# Docking_Connection.net
KiCad netlist of a schematic drawn in Altium Designer
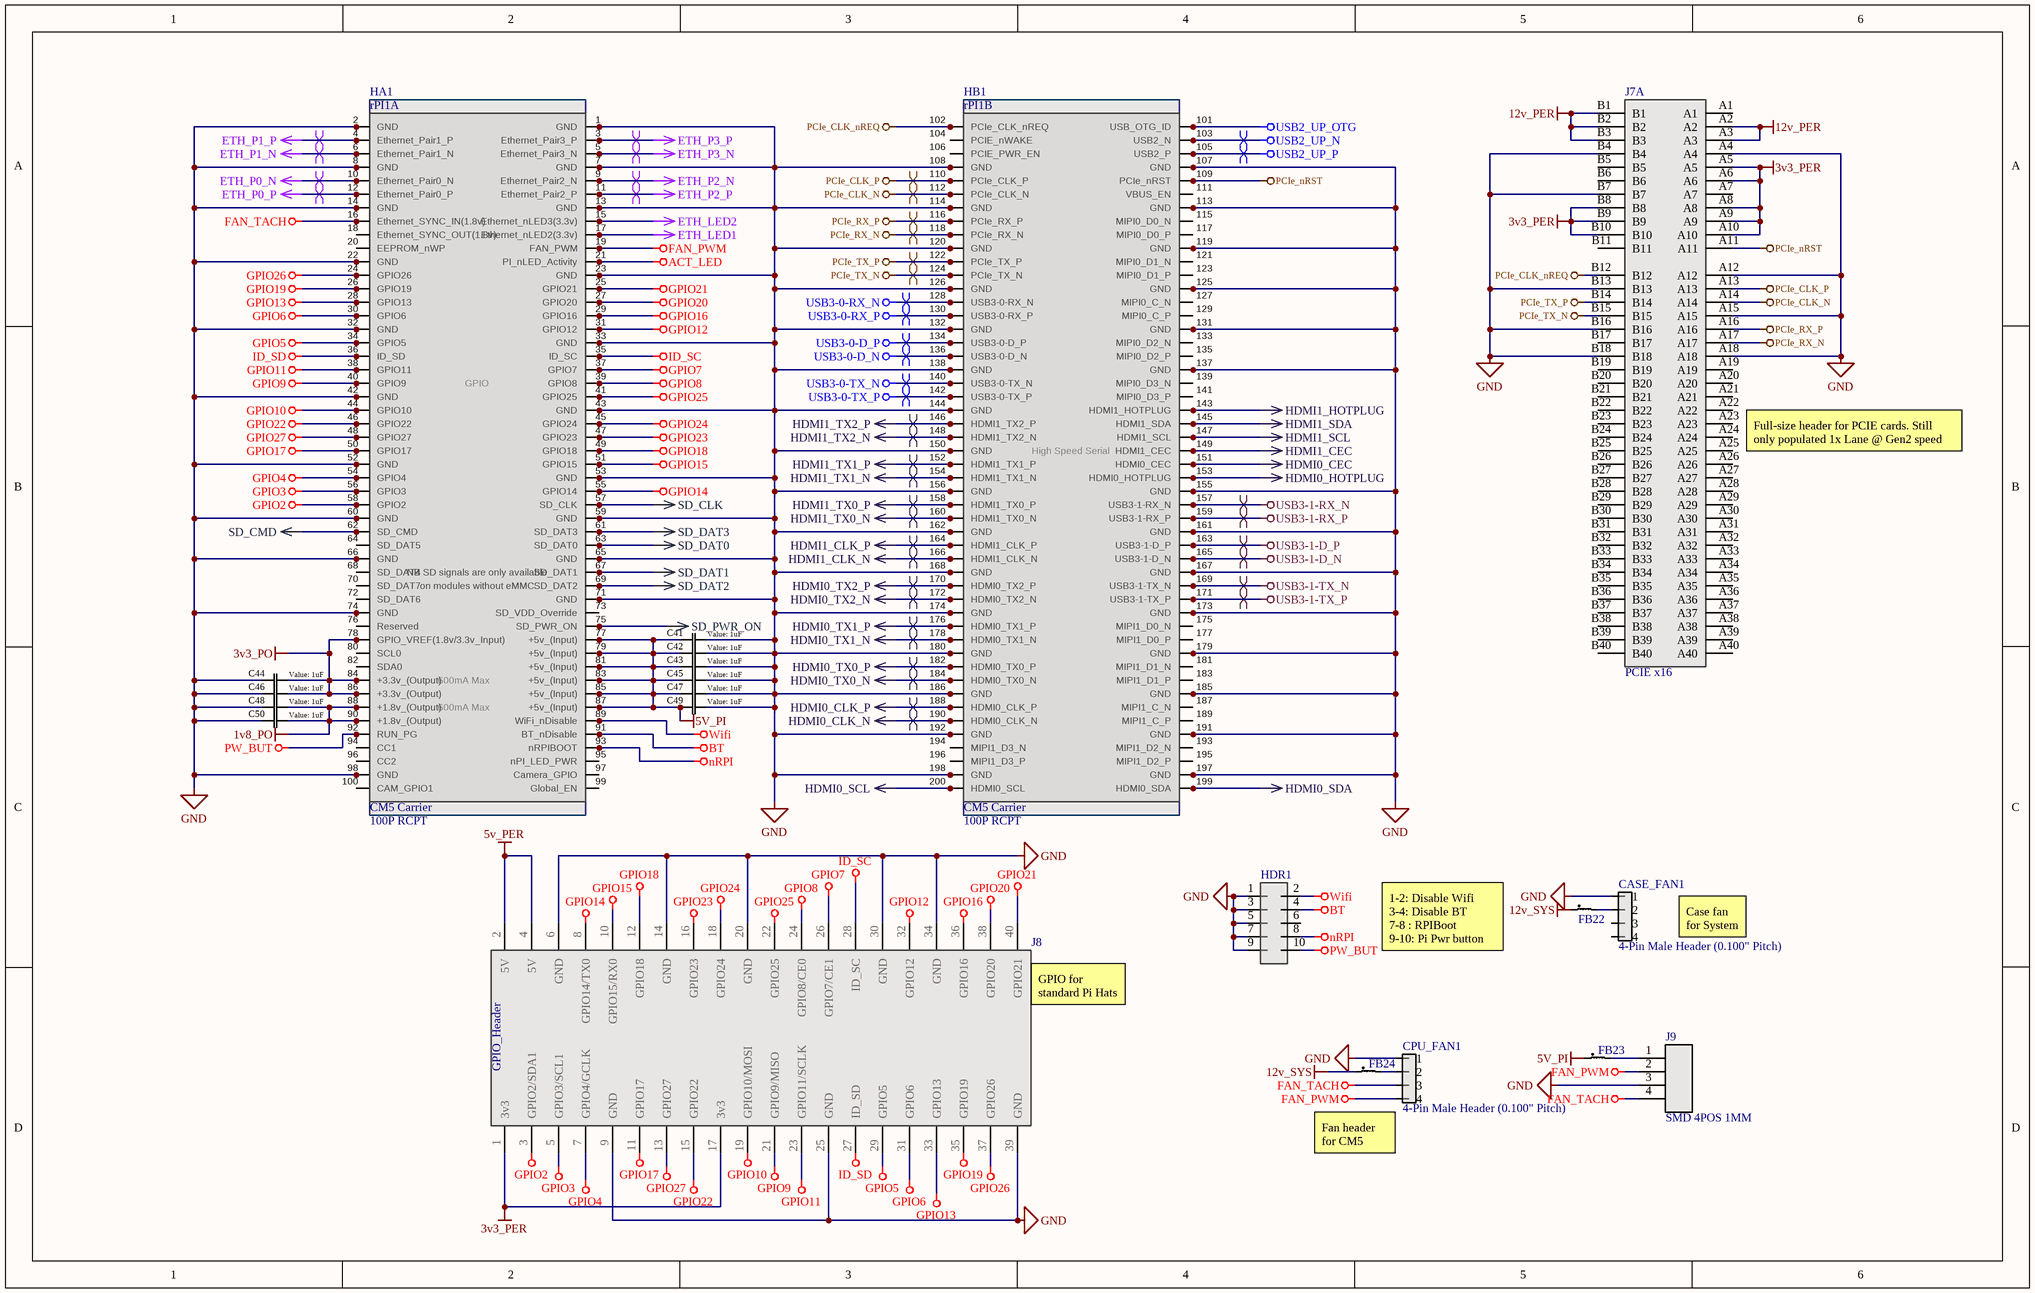
[diagram p0: Docking_Connection.SchDoc]

(export (version "E")
  (design (tool "Eeschema 10.0.6"))
  (components
    (comp (ref "C41")
      (value "1uF")
      (footprint "0603")
      (fields
        (field (name "VOLTAGE") "6V")
        (field (name "TOLERANCE") "5%")
        (field (name "Comment") "Generic Capacitor")
      )
      (libsource (lib "Capacitors") (part "Generic Capacitor"))
    )
    (comp (ref "C42")
      (value "1uF")
      (footprint "0603")
      (fields
        (field (name "VOLTAGE") "6V")
        (field (name "TOLERANCE") "5%")
        (field (name "Comment") "Generic Capacitor")
      )
      (libsource (lib "Capacitors") (part "Generic Capacitor"))
    )
    (comp (ref "C43")
      (value "1uF")
      (footprint "0603")
      (fields
        (field (name "VOLTAGE") "6V")
        (field (name "TOLERANCE") "5%")
        (field (name "Comment") "Generic Capacitor")
      )
      (libsource (lib "Capacitors") (part "Generic Capacitor"))
    )
    (comp (ref "C44")
      (value "1uF")
      (footprint "0603")
      (fields
        (field (name "VOLTAGE") "6V")
        (field (name "TOLERANCE") "5%")
        (field (name "Comment") "Generic Capacitor")
      )
      (libsource (lib "Capacitors") (part "Generic Capacitor"))
    )
    (comp (ref "C45")
      (value "1uF")
      (footprint "0603")
      (fields
        (field (name "VOLTAGE") "6V")
        (field (name "TOLERANCE") "5%")
        (field (name "Comment") "Generic Capacitor")
      )
      (libsource (lib "Capacitors") (part "Generic Capacitor"))
    )
    (comp (ref "C46")
      (value "1uF")
      (footprint "0603")
      (fields
        (field (name "VOLTAGE") "6V")
        (field (name "TOLERANCE") "5%")
        (field (name "Comment") "Generic Capacitor")
      )
      (libsource (lib "Capacitors") (part "Generic Capacitor"))
    )
    (comp (ref "C47")
      (value "1uF")
      (footprint "0603")
      (fields
        (field (name "VOLTAGE") "6V")
        (field (name "TOLERANCE") "5%")
        (field (name "Comment") "Generic Capacitor")
      )
      (libsource (lib "Capacitors") (part "Generic Capacitor"))
    )
    (comp (ref "C48")
      (value "1uF")
      (footprint "0603")
      (fields
        (field (name "VOLTAGE") "6V")
        (field (name "TOLERANCE") "5%")
        (field (name "Comment") "Generic Capacitor")
      )
      (libsource (lib "Capacitors") (part "Generic Capacitor"))
    )
    (comp (ref "C49")
      (value "1uF")
      (footprint "0603")
      (fields
        (field (name "VOLTAGE") "6V")
        (field (name "TOLERANCE") "5%")
        (field (name "Comment") "Generic Capacitor")
      )
      (libsource (lib "Capacitors") (part "Generic Capacitor"))
    )
    (comp (ref "C50")
      (value "1uF")
      (footprint "0603")
      (fields
        (field (name "VOLTAGE") "6V")
        (field (name "TOLERANCE") "5%")
        (field (name "Comment") "Generic Capacitor")
      )
      (libsource (lib "Capacitors") (part "Generic Capacitor"))
    )
    (comp (ref "CASE_FAN1")
      (value "4-Pin Male Header (0.100\" Pitch)")
      (footprint "TSW-104-07-T-S")
      (description "Connector Header Through Hole 4 position 0.100\" (2.54mm)")
      (libsource (lib "Connectors") (part "TSW-104-07-T-S"))
    )
    (comp (ref "CPU_FAN1")
      (value "4-Pin Male Header (0.100\" Pitch)")
      (footprint "TSW-104-07-T-S")
      (description "Connector Header Through Hole 4 position 0.100\" (2.54mm)")
      (libsource (lib "Connectors") (part "TSW-104-07-T-S"))
    )
    (comp (ref "FB22")
      (value "0603 Ferrite")
      (footprint "0603")
      (description "120 Ohms @ 100 MHz 1 Signal Line Ferrite Bead 0603 (1608 Metric) 500mA 180mOhm")
      (fields
        (field (name "MANUFACTURER") "Pulse")
        (field (name "MANUFACTURER PART NUMBER") "PE-0603FB121ST")
      )
      (libsource (lib "Inductors") (part "PE-0603FB121ST"))
    )
    (comp (ref "FB23")
      (value "0603 Ferrite")
      (footprint "0603")
      (description "120 Ohms @ 100 MHz 1 Signal Line Ferrite Bead 0603 (1608 Metric) 500mA 180mOhm")
      (fields
        (field (name "MANUFACTURER") "Pulse")
        (field (name "MANUFACTURER PART NUMBER") "PE-0603FB121ST")
      )
      (libsource (lib "Inductors") (part "PE-0603FB121ST"))
    )
    (comp (ref "FB24")
      (value "0603 Ferrite")
      (footprint "0603")
      (description "120 Ohms @ 100 MHz 1 Signal Line Ferrite Bead 0603 (1608 Metric) 500mA 180mOhm")
      (fields
        (field (name "MANUFACTURER") "Pulse")
        (field (name "MANUFACTURER PART NUMBER") "PE-0603FB121ST")
      )
      (libsource (lib "Inductors") (part "PE-0603FB121ST"))
    )
    (comp (ref "HA1")
      (value "100P RCPT")
      (footprint "DF40HC(3.0)-100DS-0.4V(51)")
      (description "100 Position Connector Receptacle, Center Strip Contacts Surface Mount Gold")
      (fields (field (name "MF") "Hirose") (field (name "MP") "DF40C-100DS-0.4V(51)"))
      (libsource (lib "Connectors") (part "DF40-100DS RCPT_1"))
    )
    (comp (ref "HB1")
      (value "100P RCPT")
      (footprint "DF40HC(3.0)-100DS-0.4V(51)")
      (description "100 Position Connector Receptacle, Center Strip Contacts Surface Mount Gold")
      (fields (field (name "MF") "Hirose") (field (name "MP") "DF40C-100DS-0.4V(51)"))
      (libsource (lib "Connectors") (part "DF40-100DS RCPT_1"))
    )
    (comp (ref "HDR1")
      (value "10pinMobo")
      (footprint "10pinMobo")
      (description "10pin motherboard jack")
      (libsource (lib "Connectors") (part "10pinMobo"))
    )
    (comp (ref "J7")
      (value "PCIE x16")
      (footprint "10018783-10203TLF")
      (description "164 Position Female Connector PCI Express™ Gold 0.039\" (1.00mm) Black")
      (fields (field (name "MF") "Amphenol ICC") (field (name "MP") "10018783-10203TLF"))
      (libsource (lib "Connectors") (part "10018783-10203TLF"))
    )
    (comp (ref "J8")
      (value "rPi Zero Carrier")
      (footprint "rPiHeader")
      (description "Raspberry Pi Zero/W/2W\r\nHeader, debug-pads, & mounting")
      (libsource (lib "SOC_Carrier") (part "RP-Zero_1"))
    )
    (comp (ref "J9")
      (value "SMD 4POS 1MM")
      (footprint "CONN4_BM04B-SRSS_JST")
      (description "Connector Header Surface Mount 4 position 0.039\" (1.00mm)")
      (libsource (lib "Connectors") (part "BM04B-SRSS-TB"))
    )
    (comp (ref "rPI1")
      (value "CM5 Carrier")
      (footprint "CM4-FTPD")
      (description "Compute Module 5 Footprint\r\nOverlap Hirose 100P connector over pads to place actual components")
      (libsource (lib "Misc ICs") (part "RP-CM5"))
    )
  )
  (nets
    (net (code "1") (name "1v8_PO") (class "Default")
      (node (ref "C48") (pin "1") (pinfunction "1_1") (pintype "passive"))
      (node (ref "C50") (pin "1") (pinfunction "1_1") (pintype "passive"))
      (node (ref "HA1") (pin "88") (pinfunction "88_88") (pintype "passive"))
      (node (ref "HA1") (pin "90") (pinfunction "90_90") (pintype "passive"))
      (node (ref "rPI1") (pin "88") (pinfunction "+1.8v_(Output)_88") (pintype "passive"))
      (node (ref "rPI1") (pin "90") (pinfunction "+1.8v_(Output)_90") (pintype "passive"))
    )
    (net (code "2") (name "3v3_PER") (class "Default")
      (node (ref "J7") (pin "A10") (pinfunction "A10_A10") (pintype "passive"))
      (node (ref "J7") (pin "A5") (pinfunction "A5_A5") (pintype "passive"))
      (node (ref "J7") (pin "A6") (pinfunction "A6_A6") (pintype "passive"))
      (node (ref "J7") (pin "A8") (pinfunction "A8_A8") (pintype "passive"))
      (node (ref "J7") (pin "A9") (pinfunction "A9_A9") (pintype "passive"))
      (node (ref "J7") (pin "B10") (pinfunction "B10_B10") (pintype "passive"))
      (node (ref "J7") (pin "B8") (pinfunction "B8_B8") (pintype "passive"))
      (node (ref "J7") (pin "B9") (pinfunction "B9_B9") (pintype "passive"))
      (node (ref "J8") (pin "1") (pinfunction "3v3_1") (pintype "passive"))
      (node (ref "J8") (pin "17") (pinfunction "3v3_17") (pintype "passive"))
    )
    (net (code "3") (name "3v3_PO") (class "Default")
      (node (ref "C44") (pin "1") (pinfunction "1_1") (pintype "passive"))
      (node (ref "C46") (pin "1") (pinfunction "1_1") (pintype "passive"))
      (node (ref "HA1") (pin "78") (pinfunction "78_78") (pintype "passive"))
      (node (ref "HA1") (pin "84") (pinfunction "84_84") (pintype "passive"))
      (node (ref "HA1") (pin "86") (pinfunction "86_86") (pintype "passive"))
      (node (ref "rPI1") (pin "78") (pinfunction "GPIO_VREF(1.8v/3.3v_Input)_78") (pintype "passive"))
      (node (ref "rPI1") (pin "84") (pinfunction "+3.3v_(Output)_84") (pintype "passive"))
      (node (ref "rPI1") (pin "86") (pinfunction "+3.3v_(Output)_86") (pintype "passive"))
    )
    (net (code "4") (name "5V_PI") (class "Default")
      (node (ref "C41") (pin "2") (pinfunction "2_2") (pintype "passive"))
      (node (ref "C42") (pin "2") (pinfunction "2_2") (pintype "passive"))
      (node (ref "C43") (pin "2") (pinfunction "2_2") (pintype "passive"))
      (node (ref "C45") (pin "2") (pinfunction "2_2") (pintype "passive"))
      (node (ref "C47") (pin "2") (pinfunction "2_2") (pintype "passive"))
      (node (ref "C49") (pin "2") (pinfunction "2_2") (pintype "passive"))
      (node (ref "FB23") (pin "1") (pinfunction "1_1") (pintype "passive"))
      (node (ref "HA1") (pin "77") (pinfunction "77_77") (pintype "passive"))
      (node (ref "HA1") (pin "79") (pinfunction "79_79") (pintype "passive"))
      (node (ref "HA1") (pin "81") (pinfunction "81_81") (pintype "passive"))
      (node (ref "HA1") (pin "83") (pinfunction "83_83") (pintype "passive"))
      (node (ref "HA1") (pin "85") (pinfunction "85_85") (pintype "passive"))
      (node (ref "HA1") (pin "87") (pinfunction "87_87") (pintype "passive"))
      (node (ref "rPI1") (pin "77") (pinfunction "+5v_(Input)_77") (pintype "passive"))
      (node (ref "rPI1") (pin "79") (pinfunction "+5v_(Input)_79") (pintype "passive"))
      (node (ref "rPI1") (pin "81") (pinfunction "+5v_(Input)_81") (pintype "passive"))
      (node (ref "rPI1") (pin "83") (pinfunction "+5v_(Input)_83") (pintype "passive"))
      (node (ref "rPI1") (pin "85") (pinfunction "+5v_(Input)_85") (pintype "passive"))
      (node (ref "rPI1") (pin "87") (pinfunction "+5v_(Input)_87") (pintype "passive"))
    )
    (net (code "5") (name "5v_PER") (class "Default")
      (node (ref "J8") (pin "2") (pinfunction "5V_2") (pintype "passive"))
      (node (ref "J8") (pin "4") (pinfunction "5V_4") (pintype "passive"))
    )
    (net (code "6") (name "12v_PER") (class "Default")
      (node (ref "J7") (pin "A2") (pinfunction "A2_A2") (pintype "passive"))
      (node (ref "J7") (pin "A3") (pinfunction "A3_A3") (pintype "passive"))
      (node (ref "J7") (pin "B1") (pinfunction "B1_B1") (pintype "passive"))
      (node (ref "J7") (pin "B2") (pinfunction "B2_B2") (pintype "passive"))
      (node (ref "J7") (pin "B3") (pinfunction "B3_B3") (pintype "passive"))
    )
    (net (code "7") (name "12v_SYS") (class "Default")
      (node (ref "FB22") (pin "1") (pinfunction "1_1") (pintype "passive"))
      (node (ref "FB24") (pin "1") (pinfunction "1_1") (pintype "passive"))
    )
    (net (code "8") (name "ACT_LED") (class "Default")
      (node (ref "HA1") (pin "21") (pinfunction "21_21") (pintype "passive"))
      (node (ref "rPI1") (pin "21") (pinfunction "PI_nLED_Activity_21") (pintype "passive"))
    )
    (net (code "9") (name "BT") (class "Default")
      (node (ref "HA1") (pin "91") (pinfunction "91_91") (pintype "passive"))
      (node (ref "HDR1") (pin "4") (pinfunction "4_4") (pintype "passive"))
      (node (ref "rPI1") (pin "91") (pinfunction "BT_nDisable_91") (pintype "passive"))
    )
    (net (code "10") (name "ETH_LED1") (class "Default")
      (node (ref "HA1") (pin "17") (pinfunction "17_17") (pintype "passive"))
      (node (ref "rPI1") (pin "17") (pinfunction "Ethernet_nLED2(3.3v)_17") (pintype "passive"))
    )
    (net (code "11") (name "ETH_LED2") (class "Default")
      (node (ref "HA1") (pin "15") (pinfunction "15_15") (pintype "passive"))
      (node (ref "rPI1") (pin "15") (pinfunction "Ethernet_nLED3(3.3v)_15") (pintype "passive"))
    )
    (net (code "12") (name "ETH_P0_N") (class "Default")
      (node (ref "HA1") (pin "10") (pinfunction "10_10") (pintype "passive"))
      (node (ref "rPI1") (pin "10") (pinfunction "Ethernet_Pair0_N_10") (pintype "passive"))
    )
    (net (code "13") (name "ETH_P0_P") (class "Default")
      (node (ref "HA1") (pin "12") (pinfunction "12_12") (pintype "passive"))
      (node (ref "rPI1") (pin "12") (pinfunction "Ethernet_Pair0_P_12") (pintype "passive"))
    )
    (net (code "14") (name "ETH_P1_N") (class "Default")
      (node (ref "HA1") (pin "6") (pinfunction "6_6") (pintype "passive"))
      (node (ref "rPI1") (pin "6") (pinfunction "Ethernet_Pair1_N_6") (pintype "passive"))
    )
    (net (code "15") (name "ETH_P1_P") (class "Default")
      (node (ref "HA1") (pin "4") (pinfunction "4_4") (pintype "passive"))
      (node (ref "rPI1") (pin "4") (pinfunction "Ethernet_Pair1_P_4") (pintype "passive"))
    )
    (net (code "16") (name "ETH_P2_N") (class "Default")
      (node (ref "HA1") (pin "9") (pinfunction "9_9") (pintype "passive"))
      (node (ref "rPI1") (pin "9") (pinfunction "Ethernet_Pair2_N_9") (pintype "passive"))
    )
    (net (code "17") (name "ETH_P2_P") (class "Default")
      (node (ref "HA1") (pin "11") (pinfunction "11_11") (pintype "passive"))
      (node (ref "rPI1") (pin "11") (pinfunction "Ethernet_Pair2_P_11") (pintype "passive"))
    )
    (net (code "18") (name "ETH_P3_N") (class "Default")
      (node (ref "HA1") (pin "5") (pinfunction "5_5") (pintype "passive"))
      (node (ref "rPI1") (pin "5") (pinfunction "Ethernet_Pair3_N_5") (pintype "passive"))
    )
    (net (code "19") (name "ETH_P3_P") (class "Default")
      (node (ref "HA1") (pin "3") (pinfunction "3_3") (pintype "passive"))
      (node (ref "rPI1") (pin "3") (pinfunction "Ethernet_Pair3_P_3") (pintype "passive"))
    )
    (net (code "20") (name "FAN_PWM") (class "Default")
      (node (ref "CPU_FAN1") (pin "4") (pinfunction "4_4") (pintype "passive"))
      (node (ref "HA1") (pin "19") (pinfunction "19_19") (pintype "passive"))
      (node (ref "J9") (pin "2") (pinfunction "2_2") (pintype "passive"))
      (node (ref "rPI1") (pin "19") (pinfunction "FAN_PWM_19") (pintype "passive"))
    )
    (net (code "21") (name "FAN_TACH") (class "Default")
      (node (ref "CPU_FAN1") (pin "3") (pinfunction "3_3") (pintype "passive"))
      (node (ref "HA1") (pin "16") (pinfunction "16_16") (pintype "passive"))
      (node (ref "J9") (pin "4") (pinfunction "4_4") (pintype "passive"))
      (node (ref "rPI1") (pin "16") (pinfunction "Ethernet_SYNC_IN(1.8v)_16") (pintype "passive"))
    )
    (net (code "22") (name "GND") (class "Default")
      (node (ref "C41") (pin "1") (pinfunction "1_1") (pintype "passive"))
      (node (ref "C42") (pin "1") (pinfunction "1_1") (pintype "passive"))
      (node (ref "C43") (pin "1") (pinfunction "1_1") (pintype "passive"))
      (node (ref "C44") (pin "2") (pinfunction "2_2") (pintype "passive"))
      (node (ref "C45") (pin "1") (pinfunction "1_1") (pintype "passive"))
      (node (ref "C46") (pin "2") (pinfunction "2_2") (pintype "passive"))
      (node (ref "C47") (pin "1") (pinfunction "1_1") (pintype "passive"))
      (node (ref "C48") (pin "2") (pinfunction "2_2") (pintype "passive"))
      (node (ref "C49") (pin "1") (pinfunction "1_1") (pintype "passive"))
      (node (ref "C50") (pin "2") (pinfunction "2_2") (pintype "passive"))
      (node (ref "CASE_FAN1") (pin "1") (pinfunction "1_1") (pintype "passive"))
      (node (ref "CPU_FAN1") (pin "1") (pinfunction "1_1") (pintype "passive"))
      (node (ref "HA1") (pin "1") (pinfunction "1_1") (pintype "passive"))
      (node (ref "HA1") (pin "13") (pinfunction "13_13") (pintype "passive"))
      (node (ref "HA1") (pin "14") (pinfunction "14_14") (pintype "passive"))
      (node (ref "HA1") (pin "2") (pinfunction "2_2") (pintype "passive"))
      (node (ref "HA1") (pin "22") (pinfunction "22_22") (pintype "passive"))
      (node (ref "HA1") (pin "23") (pinfunction "23_23") (pintype "passive"))
      (node (ref "HA1") (pin "32") (pinfunction "32_32") (pintype "passive"))
      (node (ref "HA1") (pin "33") (pinfunction "33_33") (pintype "passive"))
      (node (ref "HA1") (pin "42") (pinfunction "42_42") (pintype "passive"))
      (node (ref "HA1") (pin "43") (pinfunction "43_43") (pintype "passive"))
      (node (ref "HA1") (pin "52") (pinfunction "52_52") (pintype "passive"))
      (node (ref "HA1") (pin "53") (pinfunction "53_53") (pintype "passive"))
      (node (ref "HA1") (pin "59") (pinfunction "59_59") (pintype "passive"))
      (node (ref "HA1") (pin "60") (pinfunction "60_60") (pintype "passive"))
      (node (ref "HA1") (pin "65") (pinfunction "65_65") (pintype "passive"))
      (node (ref "HA1") (pin "66") (pinfunction "66_66") (pintype "passive"))
      (node (ref "HA1") (pin "7") (pinfunction "7_7") (pintype "passive"))
      (node (ref "HA1") (pin "71") (pinfunction "71_71") (pintype "passive"))
      (node (ref "HA1") (pin "74") (pinfunction "74_74") (pintype "passive"))
      (node (ref "HA1") (pin "8") (pinfunction "8_8") (pintype "passive"))
      (node (ref "HA1") (pin "98") (pinfunction "98_98") (pintype "passive"))
      (node (ref "HB1") (pin "13") (pinfunction "13_13") (pintype "passive"))
      (node (ref "HB1") (pin "14") (pinfunction "14_14") (pintype "passive"))
      (node (ref "HB1") (pin "19") (pinfunction "19_19") (pintype "passive"))
      (node (ref "HB1") (pin "20") (pinfunction "20_20") (pintype "passive"))
      (node (ref "HB1") (pin "25") (pinfunction "25_25") (pintype "passive"))
      (node (ref "HB1") (pin "26") (pinfunction "26_26") (pintype "passive"))
      (node (ref "HB1") (pin "31") (pinfunction "31_31") (pintype "passive"))
      (node (ref "HB1") (pin "32") (pinfunction "32_32") (pintype "passive"))
      (node (ref "HB1") (pin "37") (pinfunction "37_37") (pintype "passive"))
      (node (ref "HB1") (pin "38") (pinfunction "38_38") (pintype "passive"))
      (node (ref "HB1") (pin "44") (pinfunction "44_44") (pintype "passive"))
      (node (ref "HB1") (pin "50") (pinfunction "50_50") (pintype "passive"))
      (node (ref "HB1") (pin "55") (pinfunction "55_55") (pintype "passive"))
      (node (ref "HB1") (pin "56") (pinfunction "56_56") (pintype "passive"))
      (node (ref "HB1") (pin "61") (pinfunction "61_61") (pintype "passive"))
      (node (ref "HB1") (pin "62") (pinfunction "62_62") (pintype "passive"))
      (node (ref "HB1") (pin "67") (pinfunction "67_67") (pintype "passive"))
      (node (ref "HB1") (pin "68") (pinfunction "68_68") (pintype "passive"))
      (node (ref "HB1") (pin "7") (pinfunction "7_7") (pintype "passive"))
      (node (ref "HB1") (pin "73") (pinfunction "73_73") (pintype "passive"))
      (node (ref "HB1") (pin "74") (pinfunction "74_74") (pintype "passive"))
      (node (ref "HB1") (pin "79") (pinfunction "79_79") (pintype "passive"))
      (node (ref "HB1") (pin "8") (pinfunction "8_8") (pintype "passive"))
      (node (ref "HB1") (pin "80") (pinfunction "80_80") (pintype "passive"))
      (node (ref "HB1") (pin "85") (pinfunction "85_85") (pintype "passive"))
      (node (ref "HB1") (pin "86") (pinfunction "86_86") (pintype "passive"))
      (node (ref "HB1") (pin "91") (pinfunction "91_91") (pintype "passive"))
      (node (ref "HB1") (pin "92") (pinfunction "92_92") (pintype "passive"))
      (node (ref "HB1") (pin "97") (pinfunction "97_97") (pintype "passive"))
      (node (ref "HB1") (pin "98") (pinfunction "98_98") (pintype "passive"))
      (node (ref "HDR1") (pin "1") (pinfunction "1_1") (pintype "passive"))
      (node (ref "HDR1") (pin "3") (pinfunction "3_3") (pintype "passive"))
      (node (ref "HDR1") (pin "5") (pinfunction "5_5") (pintype "passive"))
      (node (ref "HDR1") (pin "7") (pinfunction "7_7") (pintype "passive"))
      (node (ref "HDR1") (pin "9") (pinfunction "9_9") (pintype "passive"))
      (node (ref "J7") (pin "A12") (pinfunction "A12_A12") (pintype "passive"))
      (node (ref "J7") (pin "A15") (pinfunction "A15_A15") (pintype "passive"))
      (node (ref "J7") (pin "A18") (pinfunction "A18_A18") (pintype "passive"))
      (node (ref "J7") (pin "A4") (pinfunction "A4_A4") (pintype "passive"))
      (node (ref "J7") (pin "B13") (pinfunction "B13_B13") (pintype "passive"))
      (node (ref "J7") (pin "B16") (pinfunction "B16_B16") (pintype "passive"))
      (node (ref "J7") (pin "B18") (pinfunction "B18_B18") (pintype "passive"))
      (node (ref "J7") (pin "B4") (pinfunction "B4_B4") (pintype "passive"))
      (node (ref "J7") (pin "B7") (pinfunction "B7_B7") (pintype "passive"))
      (node (ref "J8") (pin "14") (pinfunction "GND_14") (pintype "passive"))
      (node (ref "J8") (pin "20") (pinfunction "GND_20") (pintype "passive"))
      (node (ref "J8") (pin "25") (pinfunction "GND_25") (pintype "passive"))
      (node (ref "J8") (pin "30") (pinfunction "GND_30") (pintype "passive"))
      (node (ref "J8") (pin "34") (pinfunction "GND_34") (pintype "passive"))
      (node (ref "J8") (pin "39") (pinfunction "GND_39") (pintype "passive"))
      (node (ref "J8") (pin "6") (pinfunction "GND_6") (pintype "passive"))
      (node (ref "J8") (pin "9") (pinfunction "GND_9") (pintype "passive"))
      (node (ref "J9") (pin "3") (pinfunction "3_3") (pintype "passive"))
      (node (ref "rPI1") (pin "1") (pinfunction "GND_1") (pintype "passive"))
      (node (ref "rPI1") (pin "107") (pinfunction "GND_107") (pintype "passive"))
      (node (ref "rPI1") (pin "108") (pinfunction "GND_108") (pintype "passive"))
      (node (ref "rPI1") (pin "113") (pinfunction "GND_113") (pintype "passive"))
      (node (ref "rPI1") (pin "114") (pinfunction "GND_114") (pintype "passive"))
      (node (ref "rPI1") (pin "119") (pinfunction "GND_119") (pintype "passive"))
      (node (ref "rPI1") (pin "120") (pinfunction "GND_120") (pintype "passive"))
      (node (ref "rPI1") (pin "125") (pinfunction "GND_125") (pintype "passive"))
      (node (ref "rPI1") (pin "126") (pinfunction "GND_126") (pintype "passive"))
      (node (ref "rPI1") (pin "13") (pinfunction "GND_13") (pintype "passive"))
      (node (ref "rPI1") (pin "131") (pinfunction "GND_131") (pintype "passive"))
      (node (ref "rPI1") (pin "132") (pinfunction "GND_132") (pintype "passive"))
      (node (ref "rPI1") (pin "137") (pinfunction "GND_137") (pintype "passive"))
      (node (ref "rPI1") (pin "138") (pinfunction "GND_138") (pintype "passive"))
      (node (ref "rPI1") (pin "14") (pinfunction "GND_14") (pintype "passive"))
      (node (ref "rPI1") (pin "144") (pinfunction "GND_144") (pintype "passive"))
      (node (ref "rPI1") (pin "150") (pinfunction "GND_150") (pintype "passive"))
      (node (ref "rPI1") (pin "155") (pinfunction "GND_155") (pintype "passive"))
      (node (ref "rPI1") (pin "156") (pinfunction "GND_156") (pintype "passive"))
      (node (ref "rPI1") (pin "161") (pinfunction "GND_161") (pintype "passive"))
      (node (ref "rPI1") (pin "162") (pinfunction "GND_162") (pintype "passive"))
      (node (ref "rPI1") (pin "167") (pinfunction "GND_167") (pintype "passive"))
      (node (ref "rPI1") (pin "168") (pinfunction "GND_168") (pintype "passive"))
      (node (ref "rPI1") (pin "173") (pinfunction "GND_173") (pintype "passive"))
      (node (ref "rPI1") (pin "174") (pinfunction "GND_174") (pintype "passive"))
      (node (ref "rPI1") (pin "179") (pinfunction "GND_179") (pintype "passive"))
      (node (ref "rPI1") (pin "180") (pinfunction "GND_180") (pintype "passive"))
      (node (ref "rPI1") (pin "185") (pinfunction "GND_185") (pintype "passive"))
      (node (ref "rPI1") (pin "186") (pinfunction "GND_186") (pintype "passive"))
      (node (ref "rPI1") (pin "191") (pinfunction "GND_191") (pintype "passive"))
      (node (ref "rPI1") (pin "192") (pinfunction "GND_192") (pintype "passive"))
      (node (ref "rPI1") (pin "197") (pinfunction "GND_197") (pintype "passive"))
      (node (ref "rPI1") (pin "198") (pinfunction "GND_198") (pintype "passive"))
      (node (ref "rPI1") (pin "2") (pinfunction "GND_2") (pintype "passive"))
      (node (ref "rPI1") (pin "22") (pinfunction "GND_22") (pintype "passive"))
      (node (ref "rPI1") (pin "23") (pinfunction "GND_23") (pintype "passive"))
      (node (ref "rPI1") (pin "32") (pinfunction "GND_32") (pintype "passive"))
      (node (ref "rPI1") (pin "33") (pinfunction "GND_33") (pintype "passive"))
      (node (ref "rPI1") (pin "42") (pinfunction "GND_42") (pintype "passive"))
      (node (ref "rPI1") (pin "43") (pinfunction "GND_43") (pintype "passive"))
      (node (ref "rPI1") (pin "52") (pinfunction "GND_52") (pintype "passive"))
      (node (ref "rPI1") (pin "53") (pinfunction "GND_53") (pintype "passive"))
      (node (ref "rPI1") (pin "59") (pinfunction "GND_59") (pintype "passive"))
      (node (ref "rPI1") (pin "60") (pinfunction "GND_60") (pintype "passive"))
      (node (ref "rPI1") (pin "65") (pinfunction "GND_65") (pintype "passive"))
      (node (ref "rPI1") (pin "66") (pinfunction "GND_66") (pintype "passive"))
      (node (ref "rPI1") (pin "7") (pinfunction "GND_7") (pintype "passive"))
      (node (ref "rPI1") (pin "71") (pinfunction "GND_71") (pintype "passive"))
      (node (ref "rPI1") (pin "74") (pinfunction "GND_74") (pintype "passive"))
      (node (ref "rPI1") (pin "8") (pinfunction "GND_8") (pintype "passive"))
      (node (ref "rPI1") (pin "98") (pinfunction "GND_98") (pintype "passive"))
    )
    (net (code "23") (name "GPIO2") (class "Default")
      (node (ref "HA1") (pin "58") (pinfunction "58_58") (pintype "passive"))
      (node (ref "J8") (pin "3") (pinfunction "GPIO2/SDA1_3") (pintype "passive"))
      (node (ref "rPI1") (pin "58") (pinfunction "GPIO2_58") (pintype "passive"))
    )
    (net (code "24") (name "GPIO3") (class "Default")
      (node (ref "HA1") (pin "56") (pinfunction "56_56") (pintype "passive"))
      (node (ref "J8") (pin "5") (pinfunction "GPIO3/SCL1_5") (pintype "passive"))
      (node (ref "rPI1") (pin "56") (pinfunction "GPIO3_56") (pintype "passive"))
    )
    (net (code "25") (name "GPIO4") (class "Default")
      (node (ref "HA1") (pin "54") (pinfunction "54_54") (pintype "passive"))
      (node (ref "J8") (pin "7") (pinfunction "GPIO4/GCLK_7") (pintype "passive"))
      (node (ref "rPI1") (pin "54") (pinfunction "GPIO4_54") (pintype "passive"))
    )
    (net (code "26") (name "GPIO5") (class "Default")
      (node (ref "HA1") (pin "34") (pinfunction "34_34") (pintype "passive"))
      (node (ref "J8") (pin "29") (pinfunction "GPIO5_29") (pintype "passive"))
      (node (ref "rPI1") (pin "34") (pinfunction "GPIO5_34") (pintype "passive"))
    )
    (net (code "27") (name "GPIO6") (class "Default")
      (node (ref "HA1") (pin "30") (pinfunction "30_30") (pintype "passive"))
      (node (ref "J8") (pin "31") (pinfunction "GPIO6_31") (pintype "passive"))
      (node (ref "rPI1") (pin "30") (pinfunction "GPIO6_30") (pintype "passive"))
    )
    (net (code "28") (name "GPIO7") (class "Default")
      (node (ref "HA1") (pin "37") (pinfunction "37_37") (pintype "passive"))
      (node (ref "J8") (pin "26") (pinfunction "GPIO7/CE1_26") (pintype "passive"))
      (node (ref "rPI1") (pin "37") (pinfunction "GPIO7_37") (pintype "passive"))
    )
    (net (code "29") (name "GPIO8") (class "Default")
      (node (ref "HA1") (pin "39") (pinfunction "39_39") (pintype "passive"))
      (node (ref "J8") (pin "24") (pinfunction "GPIO8/CE0_24") (pintype "passive"))
      (node (ref "rPI1") (pin "39") (pinfunction "GPIO8_39") (pintype "passive"))
    )
    (net (code "30") (name "GPIO9") (class "Default")
      (node (ref "HA1") (pin "40") (pinfunction "40_40") (pintype "passive"))
      (node (ref "J8") (pin "21") (pinfunction "GPIO9/MISO_21") (pintype "passive"))
      (node (ref "rPI1") (pin "40") (pinfunction "GPIO9_40") (pintype "passive"))
    )
    (net (code "31") (name "GPIO10") (class "Default")
      (node (ref "HA1") (pin "44") (pinfunction "44_44") (pintype "passive"))
      (node (ref "J8") (pin "19") (pinfunction "GPIO10/MOSI_19") (pintype "passive"))
      (node (ref "rPI1") (pin "44") (pinfunction "GPIO10_44") (pintype "passive"))
    )
    (net (code "32") (name "GPIO11") (class "Default")
      (node (ref "HA1") (pin "38") (pinfunction "38_38") (pintype "passive"))
      (node (ref "J8") (pin "23") (pinfunction "GPIO11/SCLK_23") (pintype "passive"))
      (node (ref "rPI1") (pin "38") (pinfunction "GPIO11_38") (pintype "passive"))
    )
    (net (code "33") (name "GPIO12") (class "Default")
      (node (ref "HA1") (pin "31") (pinfunction "31_31") (pintype "passive"))
      (node (ref "J8") (pin "32") (pinfunction "GPIO12_32") (pintype "passive"))
      (node (ref "rPI1") (pin "31") (pinfunction "GPIO12_31") (pintype "passive"))
    )
    (net (code "34") (name "GPIO13") (class "Default")
      (node (ref "HA1") (pin "28") (pinfunction "28_28") (pintype "passive"))
      (node (ref "J8") (pin "33") (pinfunction "GPIO13_33") (pintype "passive"))
      (node (ref "rPI1") (pin "28") (pinfunction "GPIO13_28") (pintype "passive"))
    )
    (net (code "35") (name "GPIO14") (class "Default")
      (node (ref "HA1") (pin "55") (pinfunction "55_55") (pintype "passive"))
      (node (ref "J8") (pin "8") (pinfunction "GPIO14/TX0_8") (pintype "passive"))
      (node (ref "rPI1") (pin "55") (pinfunction "GPIO14_55") (pintype "passive"))
    )
    (net (code "36") (name "GPIO15") (class "Default")
      (node (ref "HA1") (pin "51") (pinfunction "51_51") (pintype "passive"))
      (node (ref "J8") (pin "10") (pinfunction "GPIO15/RX0_10") (pintype "passive"))
      (node (ref "rPI1") (pin "51") (pinfunction "GPIO15_51") (pintype "passive"))
    )
    (net (code "37") (name "GPIO16") (class "Default")
      (node (ref "HA1") (pin "29") (pinfunction "29_29") (pintype "passive"))
      (node (ref "J8") (pin "36") (pinfunction "GPIO16_36") (pintype "passive"))
      (node (ref "rPI1") (pin "29") (pinfunction "GPIO16_29") (pintype "passive"))
    )
    (net (code "38") (name "GPIO17") (class "Default")
      (node (ref "HA1") (pin "50") (pinfunction "50_50") (pintype "passive"))
      (node (ref "J8") (pin "11") (pinfunction "GPIO17_11") (pintype "passive"))
      (node (ref "rPI1") (pin "50") (pinfunction "GPIO17_50") (pintype "passive"))
    )
    (net (code "39") (name "GPIO18") (class "Default")
      (node (ref "HA1") (pin "49") (pinfunction "49_49") (pintype "passive"))
      (node (ref "J8") (pin "12") (pinfunction "GPIO18_12") (pintype "passive"))
      (node (ref "rPI1") (pin "49") (pinfunction "GPIO18_49") (pintype "passive"))
    )
    (net (code "40") (name "GPIO19") (class "Default")
      (node (ref "HA1") (pin "26") (pinfunction "26_26") (pintype "passive"))
      (node (ref "J8") (pin "35") (pinfunction "GPIO19_35") (pintype "passive"))
      (node (ref "rPI1") (pin "26") (pinfunction "GPIO19_26") (pintype "passive"))
    )
    (net (code "41") (name "GPIO20") (class "Default")
      (node (ref "HA1") (pin "27") (pinfunction "27_27") (pintype "passive"))
      (node (ref "J8") (pin "38") (pinfunction "GPIO20_38") (pintype "passive"))
      (node (ref "rPI1") (pin "27") (pinfunction "GPIO20_27") (pintype "passive"))
    )
    (net (code "42") (name "GPIO21") (class "Default")
      (node (ref "HA1") (pin "25") (pinfunction "25_25") (pintype "passive"))
      (node (ref "J8") (pin "40") (pinfunction "GPIO21_40") (pintype "passive"))
      (node (ref "rPI1") (pin "25") (pinfunction "GPIO21_25") (pintype "passive"))
    )
    (net (code "43") (name "GPIO22") (class "Default")
      (node (ref "HA1") (pin "46") (pinfunction "46_46") (pintype "passive"))
      (node (ref "J8") (pin "15") (pinfunction "GPIO22_15") (pintype "passive"))
      (node (ref "rPI1") (pin "46") (pinfunction "GPIO22_46") (pintype "passive"))
    )
    (net (code "44") (name "GPIO23") (class "Default")
      (node (ref "HA1") (pin "47") (pinfunction "47_47") (pintype "passive"))
      (node (ref "J8") (pin "16") (pinfunction "GPIO23_16") (pintype "passive"))
      (node (ref "rPI1") (pin "47") (pinfunction "GPIO23_47") (pintype "passive"))
    )
    (net (code "45") (name "GPIO24") (class "Default")
      (node (ref "HA1") (pin "45") (pinfunction "45_45") (pintype "passive"))
      (node (ref "J8") (pin "18") (pinfunction "GPIO24_18") (pintype "passive"))
      (node (ref "rPI1") (pin "45") (pinfunction "GPIO24_45") (pintype "passive"))
    )
    (net (code "46") (name "GPIO25") (class "Default")
      (node (ref "HA1") (pin "41") (pinfunction "41_41") (pintype "passive"))
      (node (ref "J8") (pin "22") (pinfunction "GPIO25_22") (pintype "passive"))
      (node (ref "rPI1") (pin "41") (pinfunction "GPIO25_41") (pintype "passive"))
    )
    (net (code "47") (name "GPIO26") (class "Default")
      (node (ref "HA1") (pin "24") (pinfunction "24_24") (pintype "passive"))
      (node (ref "J8") (pin "37") (pinfunction "GPIO26_37") (pintype "passive"))
      (node (ref "rPI1") (pin "24") (pinfunction "GPIO26_24") (pintype "passive"))
    )
    (net (code "48") (name "GPIO27") (class "Default")
      (node (ref "HA1") (pin "48") (pinfunction "48_48") (pintype "passive"))
      (node (ref "J8") (pin "13") (pinfunction "GPIO27_13") (pintype "passive"))
      (node (ref "rPI1") (pin "48") (pinfunction "GPIO27_48") (pintype "passive"))
    )
    (net (code "49") (name "HDMI0_CEC") (class "Default")
      (node (ref "HB1") (pin "51") (pinfunction "51_51") (pintype "passive"))
      (node (ref "rPI1") (pin "151") (pinfunction "HDMI0_CEC_151") (pintype "passive"))
    )
    (net (code "50") (name "HDMI0_CLK_N") (class "Default")
      (node (ref "HB1") (pin "90") (pinfunction "90_90") (pintype "passive"))
      (node (ref "rPI1") (pin "190") (pinfunction "HDMI0_CLK_N_190") (pintype "passive"))
    )
    (net (code "51") (name "HDMI0_CLK_P") (class "Default")
      (node (ref "HB1") (pin "88") (pinfunction "88_88") (pintype "passive"))
      (node (ref "rPI1") (pin "188") (pinfunction "HDMI0_CLK_P_188") (pintype "passive"))
    )
    (net (code "52") (name "HDMI0_HOTPLUG") (class "Default")
      (node (ref "HB1") (pin "53") (pinfunction "53_53") (pintype "passive"))
      (node (ref "rPI1") (pin "153") (pinfunction "HDMI0_HOTPLUG_153") (pintype "passive"))
    )
    (net (code "53") (name "HDMI0_SCL") (class "Default")
      (node (ref "HB1") (pin "100") (pinfunction "100_100") (pintype "passive"))
      (node (ref "rPI1") (pin "200") (pinfunction "HDMI0_SCL_200") (pintype "passive"))
    )
    (net (code "54") (name "HDMI0_SDA") (class "Default")
      (node (ref "HB1") (pin "99") (pinfunction "99_99") (pintype "passive"))
      (node (ref "rPI1") (pin "199") (pinfunction "HDMI0_SDA_199") (pintype "passive"))
    )
    (net (code "55") (name "HDMI0_TX0_N") (class "Default")
      (node (ref "HB1") (pin "84") (pinfunction "84_84") (pintype "passive"))
      (node (ref "rPI1") (pin "184") (pinfunction "HDMI0_TX0_N_184") (pintype "passive"))
    )
    (net (code "56") (name "HDMI0_TX0_P") (class "Default")
      (node (ref "HB1") (pin "82") (pinfunction "82_82") (pintype "passive"))
      (node (ref "rPI1") (pin "182") (pinfunction "HDMI0_TX0_P_182") (pintype "passive"))
    )
    (net (code "57") (name "HDMI0_TX1_N") (class "Default")
      (node (ref "HB1") (pin "78") (pinfunction "78_78") (pintype "passive"))
      (node (ref "rPI1") (pin "178") (pinfunction "HDMI0_TX1_N_178") (pintype "passive"))
    )
    (net (code "58") (name "HDMI0_TX1_P") (class "Default")
      (node (ref "HB1") (pin "76") (pinfunction "76_76") (pintype "passive"))
      (node (ref "rPI1") (pin "176") (pinfunction "HDMI0_TX1_P_176") (pintype "passive"))
    )
    (net (code "59") (name "HDMI0_TX2_N") (class "Default")
      (node (ref "HB1") (pin "72") (pinfunction "72_72") (pintype "passive"))
      (node (ref "rPI1") (pin "172") (pinfunction "HDMI0_TX2_N_172") (pintype "passive"))
    )
    (net (code "60") (name "HDMI0_TX2_P") (class "Default")
      (node (ref "HB1") (pin "70") (pinfunction "70_70") (pintype "passive"))
      (node (ref "rPI1") (pin "170") (pinfunction "HDMI0_TX2_P_170") (pintype "passive"))
    )
    (net (code "61") (name "HDMI1_CEC") (class "Default")
      (node (ref "HB1") (pin "49") (pinfunction "49_49") (pintype "passive"))
      (node (ref "rPI1") (pin "149") (pinfunction "HDMI1_CEC_149") (pintype "passive"))
    )
    (net (code "62") (name "HDMI1_CLK_N") (class "Default")
      (node (ref "HB1") (pin "66") (pinfunction "66_66") (pintype "passive"))
      (node (ref "rPI1") (pin "166") (pinfunction "HDMI1_CLK_N_166") (pintype "passive"))
    )
    (net (code "63") (name "HDMI1_CLK_P") (class "Default")
      (node (ref "HB1") (pin "64") (pinfunction "64_64") (pintype "passive"))
      (node (ref "rPI1") (pin "164") (pinfunction "HDMI1_CLK_P_164") (pintype "passive"))
    )
    (net (code "64") (name "HDMI1_HOTPLUG") (class "Default")
      (node (ref "HB1") (pin "43") (pinfunction "43_43") (pintype "passive"))
      (node (ref "rPI1") (pin "143") (pinfunction "HDMI1_HOTPLUG_143") (pintype "passive"))
    )
    (net (code "65") (name "HDMI1_SCL") (class "Default")
      (node (ref "HB1") (pin "47") (pinfunction "47_47") (pintype "passive"))
      (node (ref "rPI1") (pin "147") (pinfunction "HDMI1_SCL_147") (pintype "passive"))
    )
    (net (code "66") (name "HDMI1_SDA") (class "Default")
      (node (ref "HB1") (pin "45") (pinfunction "45_45") (pintype "passive"))
      (node (ref "rPI1") (pin "145") (pinfunction "HDMI1_SDA_145") (pintype "passive"))
    )
    (net (code "67") (name "HDMI1_TX0_N") (class "Default")
      (node (ref "HB1") (pin "60") (pinfunction "60_60") (pintype "passive"))
      (node (ref "rPI1") (pin "160") (pinfunction "HDMI1_TX0_N_160") (pintype "passive"))
    )
    (net (code "68") (name "HDMI1_TX0_P") (class "Default")
      (node (ref "HB1") (pin "58") (pinfunction "58_58") (pintype "passive"))
      (node (ref "rPI1") (pin "158") (pinfunction "HDMI1_TX0_P_158") (pintype "passive"))
    )
    (net (code "69") (name "HDMI1_TX1_N") (class "Default")
      (node (ref "HB1") (pin "54") (pinfunction "54_54") (pintype "passive"))
      (node (ref "rPI1") (pin "154") (pinfunction "HDMI1_TX1_N_154") (pintype "passive"))
    )
    (net (code "70") (name "HDMI1_TX1_P") (class "Default")
      (node (ref "HB1") (pin "52") (pinfunction "52_52") (pintype "passive"))
      (node (ref "rPI1") (pin "152") (pinfunction "HDMI1_TX1_P_152") (pintype "passive"))
    )
    (net (code "71") (name "HDMI1_TX2_N") (class "Default")
      (node (ref "HB1") (pin "48") (pinfunction "48_48") (pintype "passive"))
      (node (ref "rPI1") (pin "148") (pinfunction "HDMI1_TX2_N_148") (pintype "passive"))
    )
    (net (code "72") (name "HDMI1_TX2_P") (class "Default")
      (node (ref "HB1") (pin "46") (pinfunction "46_46") (pintype "passive"))
      (node (ref "rPI1") (pin "146") (pinfunction "HDMI1_TX2_P_146") (pintype "passive"))
    )
    (net (code "73") (name "ID_SC") (class "Default")
      (node (ref "HA1") (pin "35") (pinfunction "35_35") (pintype "passive"))
      (node (ref "J8") (pin "28") (pinfunction "ID_SC_28") (pintype "passive"))
      (node (ref "rPI1") (pin "35") (pinfunction "ID_SC_35") (pintype "passive"))
    )
    (net (code "74") (name "ID_SD") (class "Default")
      (node (ref "HA1") (pin "36") (pinfunction "36_36") (pintype "passive"))
      (node (ref "J8") (pin "27") (pinfunction "ID_SD_27") (pintype "passive"))
      (node (ref "rPI1") (pin "36") (pinfunction "ID_SD_36") (pintype "passive"))
    )
    (net (code "75") (name "Net-(CASE_FAN1-Pad2)") (class "Default")
      (node (ref "CASE_FAN1") (pin "2") (pinfunction "2_2") (pintype "passive"))
      (node (ref "FB22") (pin "2") (pinfunction "2_2") (pintype "passive"))
    )
    (net (code "76") (name "Net-(CPU_FAN1-Pad2)") (class "Default")
      (node (ref "CPU_FAN1") (pin "2") (pinfunction "2_2") (pintype "passive"))
      (node (ref "FB24") (pin "2") (pinfunction "2_2") (pintype "passive"))
    )
    (net (code "77") (name "Net-(FB23-Pad2)") (class "Default")
      (node (ref "FB23") (pin "2") (pinfunction "2_2") (pintype "passive"))
      (node (ref "J9") (pin "1") (pinfunction "1_1") (pintype "passive"))
    )
    (net (code "78") (name "Net-(rPI1A-CAM_GPIO1)") (class "Default")
      (node (ref "HA1") (pin "100") (pinfunction "100_100") (pintype "passive"))
      (node (ref "rPI1") (pin "100") (pinfunction "CAM_GPIO1_100") (pintype "passive"))
    )
    (net (code "79") (name "Net-(rPI1A-CC1)") (class "Default")
      (node (ref "HA1") (pin "94") (pinfunction "94_94") (pintype "passive"))
      (node (ref "rPI1") (pin "94") (pinfunction "CC1_94") (pintype "passive"))
    )
    (net (code "80") (name "Net-(rPI1A-CC2)") (class "Default")
      (node (ref "HA1") (pin "96") (pinfunction "96_96") (pintype "passive"))
      (node (ref "rPI1") (pin "96") (pinfunction "CC2_96") (pintype "passive"))
    )
    (net (code "81") (name "Net-(rPI1A-Camera_GPIO)") (class "Default")
      (node (ref "HA1") (pin "97") (pinfunction "97_97") (pintype "passive"))
      (node (ref "rPI1") (pin "97") (pinfunction "Camera_GPIO_97") (pintype "passive"))
    )
    (net (code "82") (name "Net-(rPI1A-EEPROM_nWP)") (class "Default")
      (node (ref "HA1") (pin "20") (pinfunction "20_20") (pintype "passive"))
      (node (ref "rPI1") (pin "20") (pinfunction "EEPROM_nWP_20") (pintype "passive"))
    )
    (net (code "83") (name "Net-(rPI1A-Ethernet_SYNC_OUT(1.8v))") (class "Default")
      (node (ref "HA1") (pin "18") (pinfunction "18_18") (pintype "passive"))
      (node (ref "rPI1") (pin "18") (pinfunction "Ethernet_SYNC_OUT(1.8v)_18") (pintype "passive"))
    )
    (net (code "84") (name "Net-(rPI1A-Global_EN)") (class "Default")
      (node (ref "HA1") (pin "99") (pinfunction "99_99") (pintype "passive"))
      (node (ref "rPI1") (pin "99") (pinfunction "Global_EN_99") (pintype "passive"))
    )
    (net (code "85") (name "Net-(rPI1A-Reserved)") (class "Default")
      (node (ref "HA1") (pin "76") (pinfunction "76_76") (pintype "passive"))
      (node (ref "rPI1") (pin "76") (pinfunction "Reserved_76") (pintype "passive"))
    )
    (net (code "86") (name "Net-(rPI1A-SCL0)") (class "Default")
      (node (ref "HA1") (pin "80") (pinfunction "80_80") (pintype "passive"))
      (node (ref "rPI1") (pin "80") (pinfunction "SCL0_80") (pintype "passive"))
    )
    (net (code "87") (name "Net-(rPI1A-SDA0)") (class "Default")
      (node (ref "HA1") (pin "82") (pinfunction "82_82") (pintype "passive"))
      (node (ref "rPI1") (pin "82") (pinfunction "SDA0_82") (pintype "passive"))
    )
    (net (code "88") (name "Net-(rPI1A-SD_DAT4)") (class "Default")
      (node (ref "HA1") (pin "68") (pinfunction "68_68") (pintype "passive"))
      (node (ref "rPI1") (pin "68") (pinfunction "SD_DAT4_68") (pintype "passive"))
    )
    (net (code "89") (name "Net-(rPI1A-SD_DAT5)") (class "Default")
      (node (ref "HA1") (pin "64") (pinfunction "64_64") (pintype "passive"))
      (node (ref "rPI1") (pin "64") (pinfunction "SD_DAT5_64") (pintype "passive"))
    )
    (net (code "90") (name "Net-(rPI1A-SD_DAT6)") (class "Default")
      (node (ref "HA1") (pin "72") (pinfunction "72_72") (pintype "passive"))
      (node (ref "rPI1") (pin "72") (pinfunction "SD_DAT6_72") (pintype "passive"))
    )
    (net (code "91") (name "Net-(rPI1A-SD_DAT7)") (class "Default")
      (node (ref "HA1") (pin "70") (pinfunction "70_70") (pintype "passive"))
      (node (ref "rPI1") (pin "70") (pinfunction "SD_DAT7_70") (pintype "passive"))
    )
    (net (code "92") (name "Net-(rPI1A-SD_VDD_Override)") (class "Default")
      (node (ref "HA1") (pin "73") (pinfunction "73_73") (pintype "passive"))
      (node (ref "rPI1") (pin "73") (pinfunction "SD_VDD_Override_73") (pintype "passive"))
    )
    (net (code "93") (name "Net-(rPI1A-nPI_LED_PWR)") (class "Default")
      (node (ref "HA1") (pin "95") (pinfunction "95_95") (pintype "passive"))
      (node (ref "rPI1") (pin "95") (pinfunction "nPI_LED_PWR_95") (pintype "passive"))
    )
    (net (code "94") (name "Net-(rPI1B-MIPI0_C_N)") (class "Default")
      (node (ref "HB1") (pin "27") (pinfunction "27_27") (pintype "passive"))
      (node (ref "rPI1") (pin "127") (pinfunction "MIPI0_C_N_127") (pintype "passive"))
    )
    (net (code "95") (name "Net-(rPI1B-MIPI0_C_P)") (class "Default")
      (node (ref "HB1") (pin "29") (pinfunction "29_29") (pintype "passive"))
      (node (ref "rPI1") (pin "129") (pinfunction "MIPI0_C_P_129") (pintype "passive"))
    )
    (net (code "96") (name "Net-(rPI1B-MIPI0_D0_N)") (class "Default")
      (node (ref "HB1") (pin "15") (pinfunction "15_15") (pintype "passive"))
      (node (ref "rPI1") (pin "115") (pinfunction "MIPI0_D0_N_115") (pintype "passive"))
    )
    (net (code "97") (name "Net-(rPI1B-MIPI0_D0_P)") (class "Default")
      (node (ref "HB1") (pin "17") (pinfunction "17_17") (pintype "passive"))
      (node (ref "rPI1") (pin "117") (pinfunction "MIPI0_D0_P_117") (pintype "passive"))
    )
    (net (code "98") (name "Net-(rPI1B-MIPI0_D1_N)") (class "Default")
      (node (ref "HB1") (pin "21") (pinfunction "21_21") (pintype "passive"))
      (node (ref "rPI1") (pin "121") (pinfunction "MIPI0_D1_N_121") (pintype "passive"))
    )
    (net (code "99") (name "Net-(rPI1B-MIPI0_D1_P)") (class "Default")
      (node (ref "HB1") (pin "23") (pinfunction "23_23") (pintype "passive"))
      (node (ref "rPI1") (pin "123") (pinfunction "MIPI0_D1_P_123") (pintype "passive"))
    )
    (net (code "100") (name "Net-(rPI1B-MIPI0_D2_N)") (class "Default")
      (node (ref "HB1") (pin "33") (pinfunction "33_33") (pintype "passive"))
      (node (ref "rPI1") (pin "133") (pinfunction "MIPI0_D2_N_133") (pintype "passive"))
    )
    (net (code "101") (name "Net-(rPI1B-MIPI0_D2_P)") (class "Default")
      (node (ref "HB1") (pin "35") (pinfunction "35_35") (pintype "passive"))
      (node (ref "rPI1") (pin "135") (pinfunction "MIPI0_D2_P_135") (pintype "passive"))
    )
    (net (code "102") (name "Net-(rPI1B-MIPI0_D3_N)") (class "Default")
      (node (ref "HB1") (pin "39") (pinfunction "39_39") (pintype "passive"))
      (node (ref "rPI1") (pin "139") (pinfunction "MIPI0_D3_N_139") (pintype "passive"))
    )
    (net (code "103") (name "Net-(rPI1B-MIPI0_D3_P)") (class "Default")
      (node (ref "HB1") (pin "41") (pinfunction "41_41") (pintype "passive"))
      (node (ref "rPI1") (pin "141") (pinfunction "MIPI0_D3_P_141") (pintype "passive"))
    )
    (net (code "104") (name "Net-(rPI1B-MIPI1_C_N)") (class "Default")
      (node (ref "HB1") (pin "87") (pinfunction "87_87") (pintype "passive"))
      (node (ref "rPI1") (pin "187") (pinfunction "MIPI1_C_N_187") (pintype "passive"))
    )
    (net (code "105") (name "Net-(rPI1B-MIPI1_C_P)") (class "Default")
      (node (ref "HB1") (pin "89") (pinfunction "89_89") (pintype "passive"))
      (node (ref "rPI1") (pin "189") (pinfunction "MIPI1_C_P_189") (pintype "passive"))
    )
    (net (code "106") (name "Net-(rPI1B-MIPI1_D0_N)") (class "Default")
      (node (ref "HB1") (pin "75") (pinfunction "75_75") (pintype "passive"))
      (node (ref "rPI1") (pin "175") (pinfunction "MIPI1_D0_N_175") (pintype "passive"))
    )
    (net (code "107") (name "Net-(rPI1B-MIPI1_D0_P)") (class "Default")
      (node (ref "HB1") (pin "77") (pinfunction "77_77") (pintype "passive"))
      (node (ref "rPI1") (pin "177") (pinfunction "MIPI1_D0_P_177") (pintype "passive"))
    )
    (net (code "108") (name "Net-(rPI1B-MIPI1_D1_N)") (class "Default")
      (node (ref "HB1") (pin "81") (pinfunction "81_81") (pintype "passive"))
      (node (ref "rPI1") (pin "181") (pinfunction "MIPI1_D1_N_181") (pintype "passive"))
    )
    (net (code "109") (name "Net-(rPI1B-MIPI1_D1_P)") (class "Default")
      (node (ref "HB1") (pin "83") (pinfunction "83_83") (pintype "passive"))
      (node (ref "rPI1") (pin "183") (pinfunction "MIPI1_D1_P_183") (pintype "passive"))
    )
    (net (code "110") (name "Net-(rPI1B-MIPI1_D2_N)") (class "Default")
      (node (ref "HB1") (pin "93") (pinfunction "93_93") (pintype "passive"))
      (node (ref "rPI1") (pin "193") (pinfunction "MIPI1_D2_N_193") (pintype "passive"))
    )
    (net (code "111") (name "Net-(rPI1B-MIPI1_D2_P)") (class "Default")
      (node (ref "HB1") (pin "95") (pinfunction "95_95") (pintype "passive"))
      (node (ref "rPI1") (pin "195") (pinfunction "MIPI1_D2_P_195") (pintype "passive"))
    )
    (net (code "112") (name "Net-(rPI1B-MIPI1_D3_N)") (class "Default")
      (node (ref "HB1") (pin "94") (pinfunction "94_94") (pintype "passive"))
      (node (ref "rPI1") (pin "194") (pinfunction "MIPI1_D3_N_194") (pintype "passive"))
    )
    (net (code "113") (name "Net-(rPI1B-MIPI1_D3_P)") (class "Default")
      (node (ref "HB1") (pin "96") (pinfunction "96_96") (pintype "passive"))
      (node (ref "rPI1") (pin "196") (pinfunction "MIPI1_D3_P_196") (pintype "passive"))
    )
    (net (code "114") (name "Net-(rPI1B-PCIE_PWR_EN)") (class "Default")
      (node (ref "HB1") (pin "6") (pinfunction "6_6") (pintype "passive"))
      (node (ref "rPI1") (pin "106") (pinfunction "PCIE_PWR_EN_106") (pintype "passive"))
    )
    (net (code "115") (name "Net-(rPI1B-PCIE_nWAKE)") (class "Default")
      (node (ref "HB1") (pin "4") (pinfunction "4_4") (pintype "passive"))
      (node (ref "rPI1") (pin "104") (pinfunction "PCIE_nWAKE_104") (pintype "passive"))
    )
    (net (code "116") (name "Net-(rPI1B-VBUS_EN)") (class "Default")
      (node (ref "HB1") (pin "11") (pinfunction "11_11") (pintype "passive"))
      (node (ref "rPI1") (pin "111") (pinfunction "VBUS_EN_111") (pintype "passive"))
    )
    (net (code "117") (name "PCIe_CLK_N") (class "Default")
      (node (ref "HB1") (pin "12") (pinfunction "12_12") (pintype "passive"))
      (node (ref "J7") (pin "A14") (pinfunction "A14_A14") (pintype "passive"))
      (node (ref "rPI1") (pin "112") (pinfunction "PCIe_CLK_N_112") (pintype "passive"))
    )
    (net (code "118") (name "PCIe_CLK_P") (class "Default")
      (node (ref "HB1") (pin "10") (pinfunction "10_10") (pintype "passive"))
      (node (ref "J7") (pin "A13") (pinfunction "A13_A13") (pintype "passive"))
      (node (ref "rPI1") (pin "110") (pinfunction "PCIe_CLK_P_110") (pintype "passive"))
    )
    (net (code "119") (name "PCIe_CLK_nREQ") (class "Default")
      (node (ref "HB1") (pin "2") (pinfunction "2_2") (pintype "passive"))
      (node (ref "J7") (pin "B12") (pinfunction "B12_B12") (pintype "passive"))
      (node (ref "rPI1") (pin "102") (pinfunction "PCIe_CLK_nREQ_102") (pintype "passive"))
    )
    (net (code "120") (name "PCIe_RX_N") (class "Default")
      (node (ref "HB1") (pin "18") (pinfunction "18_18") (pintype "passive"))
      (node (ref "J7") (pin "A17") (pinfunction "A17_A17") (pintype "passive"))
      (node (ref "rPI1") (pin "118") (pinfunction "PCIe_RX_N_118") (pintype "passive"))
    )
    (net (code "121") (name "PCIe_RX_P") (class "Default")
      (node (ref "HB1") (pin "16") (pinfunction "16_16") (pintype "passive"))
      (node (ref "J7") (pin "A16") (pinfunction "A16_A16") (pintype "passive"))
      (node (ref "rPI1") (pin "116") (pinfunction "PCIe_RX_P_116") (pintype "passive"))
    )
    (net (code "122") (name "PCIe_TX_N") (class "Default")
      (node (ref "HB1") (pin "24") (pinfunction "24_24") (pintype "passive"))
      (node (ref "J7") (pin "B15") (pinfunction "B15_B15") (pintype "passive"))
      (node (ref "rPI1") (pin "124") (pinfunction "PCIe_TX_N_124") (pintype "passive"))
    )
    (net (code "123") (name "PCIe_TX_P") (class "Default")
      (node (ref "HB1") (pin "22") (pinfunction "22_22") (pintype "passive"))
      (node (ref "J7") (pin "B14") (pinfunction "B14_B14") (pintype "passive"))
      (node (ref "rPI1") (pin "122") (pinfunction "PCIe_TX_P_122") (pintype "passive"))
    )
    (net (code "124") (name "PCIe_nRST") (class "Default")
      (node (ref "HB1") (pin "9") (pinfunction "9_9") (pintype "passive"))
      (node (ref "J7") (pin "A11") (pinfunction "A11_A11") (pintype "passive"))
      (node (ref "rPI1") (pin "109") (pinfunction "PCIe_nRST_109") (pintype "passive"))
    )
    (net (code "125") (name "PW_BUT") (class "Default")
      (node (ref "HA1") (pin "92") (pinfunction "92_92") (pintype "passive"))
      (node (ref "HDR1") (pin "10") (pinfunction "10_10") (pintype "passive"))
      (node (ref "rPI1") (pin "92") (pinfunction "RUN_PG_92") (pintype "passive"))
    )
    (net (code "126") (name "SD_CLK") (class "Default")
      (node (ref "HA1") (pin "57") (pinfunction "57_57") (pintype "passive"))
      (node (ref "rPI1") (pin "57") (pinfunction "SD_CLK_57") (pintype "passive"))
    )
    (net (code "127") (name "SD_CMD") (class "Default")
      (node (ref "HA1") (pin "62") (pinfunction "62_62") (pintype "passive"))
      (node (ref "rPI1") (pin "62") (pinfunction "SD_CMD_62") (pintype "passive"))
    )
    (net (code "128") (name "SD_DAT0") (class "Default")
      (node (ref "HA1") (pin "63") (pinfunction "63_63") (pintype "passive"))
      (node (ref "rPI1") (pin "63") (pinfunction "SD_DAT0_63") (pintype "passive"))
    )
    (net (code "129") (name "SD_DAT1") (class "Default")
      (node (ref "HA1") (pin "67") (pinfunction "67_67") (pintype "passive"))
      (node (ref "rPI1") (pin "67") (pinfunction "SD_DAT1_67") (pintype "passive"))
    )
    (net (code "130") (name "SD_DAT2") (class "Default")
      (node (ref "HA1") (pin "69") (pinfunction "69_69") (pintype "passive"))
      (node (ref "rPI1") (pin "69") (pinfunction "SD_DAT2_69") (pintype "passive"))
    )
    (net (code "131") (name "SD_DAT3") (class "Default")
      (node (ref "HA1") (pin "61") (pinfunction "61_61") (pintype "passive"))
      (node (ref "rPI1") (pin "61") (pinfunction "SD_DAT3_61") (pintype "passive"))
    )
    (net (code "132") (name "SD_PWR_ON") (class "Default")
      (node (ref "HA1") (pin "75") (pinfunction "75_75") (pintype "passive"))
      (node (ref "rPI1") (pin "75") (pinfunction "SD_PWR_ON_75") (pintype "passive"))
    )
    (net (code "133") (name "USB2_UP_N") (class "Default")
      (node (ref "HB1") (pin "3") (pinfunction "3_3") (pintype "passive"))
      (node (ref "rPI1") (pin "103") (pinfunction "USB2_N_103") (pintype "passive"))
    )
    (net (code "134") (name "USB2_UP_OTG") (class "Default")
      (node (ref "HB1") (pin "1") (pinfunction "1_1") (pintype "passive"))
      (node (ref "rPI1") (pin "101") (pinfunction "USB_OTG_ID_101") (pintype "passive"))
    )
    (net (code "135") (name "USB2_UP_P") (class "Default")
      (node (ref "HB1") (pin "5") (pinfunction "5_5") (pintype "passive"))
      (node (ref "rPI1") (pin "105") (pinfunction "USB2_P_105") (pintype "passive"))
    )
    (net (code "136") (name "USB3-0-D_N") (class "Default")
      (node (ref "HB1") (pin "36") (pinfunction "36_36") (pintype "passive"))
      (node (ref "rPI1") (pin "136") (pinfunction "USB3-0-D_N_136") (pintype "passive"))
    )
    (net (code "137") (name "USB3-0-D_P") (class "Default")
      (node (ref "HB1") (pin "34") (pinfunction "34_34") (pintype "passive"))
      (node (ref "rPI1") (pin "134") (pinfunction "USB3-0-D_P_134") (pintype "passive"))
    )
    (net (code "138") (name "USB3-0-RX_N") (class "Default")
      (node (ref "HB1") (pin "28") (pinfunction "28_28") (pintype "passive"))
      (node (ref "rPI1") (pin "128") (pinfunction "USB3-0-RX_N_128") (pintype "passive"))
    )
    (net (code "139") (name "USB3-0-RX_P") (class "Default")
      (node (ref "HB1") (pin "30") (pinfunction "30_30") (pintype "passive"))
      (node (ref "rPI1") (pin "130") (pinfunction "USB3-0-RX_P_130") (pintype "passive"))
    )
    (net (code "140") (name "USB3-0-TX_N") (class "Default")
      (node (ref "HB1") (pin "40") (pinfunction "40_40") (pintype "passive"))
      (node (ref "rPI1") (pin "140") (pinfunction "USB3-0-TX_N_140") (pintype "passive"))
    )
    (net (code "141") (name "USB3-0-TX_P") (class "Default")
      (node (ref "HB1") (pin "42") (pinfunction "42_42") (pintype "passive"))
      (node (ref "rPI1") (pin "142") (pinfunction "USB3-0-TX_P_142") (pintype "passive"))
    )
    (net (code "142") (name "USB3-1-D_N") (class "Default")
      (node (ref "HB1") (pin "65") (pinfunction "65_65") (pintype "passive"))
      (node (ref "rPI1") (pin "165") (pinfunction "USB3-1-D_N_165") (pintype "passive"))
    )
    (net (code "143") (name "USB3-1-D_P") (class "Default")
      (node (ref "HB1") (pin "63") (pinfunction "63_63") (pintype "passive"))
      (node (ref "rPI1") (pin "163") (pinfunction "USB3-1-D_P_163") (pintype "passive"))
    )
    (net (code "144") (name "USB3-1-RX_N") (class "Default")
      (node (ref "HB1") (pin "57") (pinfunction "57_57") (pintype "passive"))
      (node (ref "rPI1") (pin "157") (pinfunction "USB3-1-RX_N_157") (pintype "passive"))
    )
    (net (code "145") (name "USB3-1-RX_P") (class "Default")
      (node (ref "HB1") (pin "59") (pinfunction "59_59") (pintype "passive"))
      (node (ref "rPI1") (pin "159") (pinfunction "USB3-1-RX_P_159") (pintype "passive"))
    )
    (net (code "146") (name "USB3-1-TX_N") (class "Default")
      (node (ref "HB1") (pin "69") (pinfunction "69_69") (pintype "passive"))
      (node (ref "rPI1") (pin "169") (pinfunction "USB3-1-TX_N_169") (pintype "passive"))
    )
    (net (code "147") (name "USB3-1-TX_P") (class "Default")
      (node (ref "HB1") (pin "71") (pinfunction "71_71") (pintype "passive"))
      (node (ref "rPI1") (pin "171") (pinfunction "USB3-1-TX_P_171") (pintype "passive"))
    )
    (net (code "148") (name "Wifi") (class "Default")
      (node (ref "HA1") (pin "89") (pinfunction "89_89") (pintype "passive"))
      (node (ref "HDR1") (pin "2") (pinfunction "2_2") (pintype "passive"))
      (node (ref "rPI1") (pin "89") (pinfunction "WiFi_nDisable_89") (pintype "passive"))
    )
    (net (code "149") (name "nRPI") (class "Default")
      (node (ref "HA1") (pin "93") (pinfunction "93_93") (pintype "passive"))
      (node (ref "HDR1") (pin "8") (pinfunction "8_8") (pintype "passive"))
      (node (ref "rPI1") (pin "93") (pinfunction "nRPIBOOT_93") (pintype "passive"))
    )
    (net (code "150") (name "unconnected-(CASE_FAN1-Pad3)") (class "Default")
      (node (ref "CASE_FAN1") (pin "3") (pinfunction "3_3") (pintype "passive"))
    )
    (net (code "151") (name "unconnected-(CASE_FAN1-Pad4)") (class "Default")
      (node (ref "CASE_FAN1") (pin "4") (pinfunction "4_4") (pintype "passive"))
    )
    (net (code "152") (name "unconnected-(HDR1-Pad6)") (class "Default")
      (node (ref "HDR1") (pin "6") (pinfunction "6_6") (pintype "passive"))
    )
    (net (code "153") (name "unconnected-(J7-PadA1)") (class "Default")
      (node (ref "J7") (pin "A1") (pinfunction "A1_A1") (pintype "passive"))
    )
    (net (code "154") (name "unconnected-(J7-PadA7)") (class "Default")
      (node (ref "J7") (pin "A7") (pinfunction "A7_A7") (pintype "passive"))
    )
    (net (code "155") (name "unconnected-(J7-PadA19)") (class "Default")
      (node (ref "J7") (pin "A19") (pinfunction "A19_A19") (pintype "passive"))
    )
    (net (code "156") (name "unconnected-(J7-PadA20)") (class "Default")
      (node (ref "J7") (pin "A20") (pinfunction "A20_A20") (pintype "passive"))
    )
    (net (code "157") (name "unconnected-(J7-PadA21)") (class "Default")
      (node (ref "J7") (pin "A21") (pinfunction "A21_A21") (pintype "passive"))
    )
    (net (code "158") (name "unconnected-(J7-PadA22)") (class "Default")
      (node (ref "J7") (pin "A22") (pinfunction "A22_A22") (pintype "passive"))
    )
    (net (code "159") (name "unconnected-(J7-PadA23)") (class "Default")
      (node (ref "J7") (pin "A23") (pinfunction "A23_A23") (pintype "passive"))
    )
    (net (code "160") (name "unconnected-(J7-PadA24)") (class "Default")
      (node (ref "J7") (pin "A24") (pinfunction "A24_A24") (pintype "passive"))
    )
    (net (code "161") (name "unconnected-(J7-PadA25)") (class "Default")
      (node (ref "J7") (pin "A25") (pinfunction "A25_A25") (pintype "passive"))
    )
    (net (code "162") (name "unconnected-(J7-PadA26)") (class "Default")
      (node (ref "J7") (pin "A26") (pinfunction "A26_A26") (pintype "passive"))
    )
    (net (code "163") (name "unconnected-(J7-PadA27)") (class "Default")
      (node (ref "J7") (pin "A27") (pinfunction "A27_A27") (pintype "passive"))
    )
    (net (code "164") (name "unconnected-(J7-PadA28)") (class "Default")
      (node (ref "J7") (pin "A28") (pinfunction "A28_A28") (pintype "passive"))
    )
    (net (code "165") (name "unconnected-(J7-PadA29)") (class "Default")
      (node (ref "J7") (pin "A29") (pinfunction "A29_A29") (pintype "passive"))
    )
    (net (code "166") (name "unconnected-(J7-PadA30)") (class "Default")
      (node (ref "J7") (pin "A30") (pinfunction "A30_A30") (pintype "passive"))
    )
    (net (code "167") (name "unconnected-(J7-PadA31)") (class "Default")
      (node (ref "J7") (pin "A31") (pinfunction "A31_A31") (pintype "passive"))
    )
    (net (code "168") (name "unconnected-(J7-PadA32)") (class "Default")
      (node (ref "J7") (pin "A32") (pinfunction "A32_A32") (pintype "passive"))
    )
    (net (code "169") (name "unconnected-(J7-PadA33)") (class "Default")
      (node (ref "J7") (pin "A33") (pinfunction "A33_A33") (pintype "passive"))
    )
    (net (code "170") (name "unconnected-(J7-PadA34)") (class "Default")
      (node (ref "J7") (pin "A34") (pinfunction "A34_A34") (pintype "passive"))
    )
    (net (code "171") (name "unconnected-(J7-PadA35)") (class "Default")
      (node (ref "J7") (pin "A35") (pinfunction "A35_A35") (pintype "passive"))
    )
    (net (code "172") (name "unconnected-(J7-PadA36)") (class "Default")
      (node (ref "J7") (pin "A36") (pinfunction "A36_A36") (pintype "passive"))
    )
    (net (code "173") (name "unconnected-(J7-PadA37)") (class "Default")
      (node (ref "J7") (pin "A37") (pinfunction "A37_A37") (pintype "passive"))
    )
    (net (code "174") (name "unconnected-(J7-PadA38)") (class "Default")
      (node (ref "J7") (pin "A38") (pinfunction "A38_A38") (pintype "passive"))
    )
    (net (code "175") (name "unconnected-(J7-PadA39)") (class "Default")
      (node (ref "J7") (pin "A39") (pinfunction "A39_A39") (pintype "passive"))
    )
    (net (code "176") (name "unconnected-(J7-PadA40)") (class "Default")
      (node (ref "J7") (pin "A40") (pinfunction "A40_A40") (pintype "passive"))
    )
    (net (code "177") (name "unconnected-(J7-PadB5)") (class "Default")
      (node (ref "J7") (pin "B5") (pinfunction "B5_B5") (pintype "passive"))
    )
    (net (code "178") (name "unconnected-(J7-PadB6)") (class "Default")
      (node (ref "J7") (pin "B6") (pinfunction "B6_B6") (pintype "passive"))
    )
    (net (code "179") (name "unconnected-(J7-PadB11)") (class "Default")
      (node (ref "J7") (pin "B11") (pinfunction "B11_B11") (pintype "passive"))
    )
    (net (code "180") (name "unconnected-(J7-PadB17)") (class "Default")
      (node (ref "J7") (pin "B17") (pinfunction "B17_B17") (pintype "passive"))
    )
    (net (code "181") (name "unconnected-(J7-PadB19)") (class "Default")
      (node (ref "J7") (pin "B19") (pinfunction "B19_B19") (pintype "passive"))
    )
    (net (code "182") (name "unconnected-(J7-PadB20)") (class "Default")
      (node (ref "J7") (pin "B20") (pinfunction "B20_B20") (pintype "passive"))
    )
    (net (code "183") (name "unconnected-(J7-PadB21)") (class "Default")
      (node (ref "J7") (pin "B21") (pinfunction "B21_B21") (pintype "passive"))
    )
    (net (code "184") (name "unconnected-(J7-PadB22)") (class "Default")
      (node (ref "J7") (pin "B22") (pinfunction "B22_B22") (pintype "passive"))
    )
    (net (code "185") (name "unconnected-(J7-PadB23)") (class "Default")
      (node (ref "J7") (pin "B23") (pinfunction "B23_B23") (pintype "passive"))
    )
    (net (code "186") (name "unconnected-(J7-PadB24)") (class "Default")
      (node (ref "J7") (pin "B24") (pinfunction "B24_B24") (pintype "passive"))
    )
    (net (code "187") (name "unconnected-(J7-PadB25)") (class "Default")
      (node (ref "J7") (pin "B25") (pinfunction "B25_B25") (pintype "passive"))
    )
    (net (code "188") (name "unconnected-(J7-PadB26)") (class "Default")
      (node (ref "J7") (pin "B26") (pinfunction "B26_B26") (pintype "passive"))
    )
    (net (code "189") (name "unconnected-(J7-PadB27)") (class "Default")
      (node (ref "J7") (pin "B27") (pinfunction "B27_B27") (pintype "passive"))
    )
    (net (code "190") (name "unconnected-(J7-PadB28)") (class "Default")
      (node (ref "J7") (pin "B28") (pinfunction "B28_B28") (pintype "passive"))
    )
    (net (code "191") (name "unconnected-(J7-PadB29)") (class "Default")
      (node (ref "J7") (pin "B29") (pinfunction "B29_B29") (pintype "passive"))
    )
    (net (code "192") (name "unconnected-(J7-PadB30)") (class "Default")
      (node (ref "J7") (pin "B30") (pinfunction "B30_B30") (pintype "passive"))
    )
    (net (code "193") (name "unconnected-(J7-PadB31)") (class "Default")
      (node (ref "J7") (pin "B31") (pinfunction "B31_B31") (pintype "passive"))
    )
    (net (code "194") (name "unconnected-(J7-PadB32)") (class "Default")
      (node (ref "J7") (pin "B32") (pinfunction "B32_B32") (pintype "passive"))
    )
    (net (code "195") (name "unconnected-(J7-PadB33)") (class "Default")
      (node (ref "J7") (pin "B33") (pinfunction "B33_B33") (pintype "passive"))
    )
    (net (code "196") (name "unconnected-(J7-PadB34)") (class "Default")
      (node (ref "J7") (pin "B34") (pinfunction "B34_B34") (pintype "passive"))
    )
    (net (code "197") (name "unconnected-(J7-PadB35)") (class "Default")
      (node (ref "J7") (pin "B35") (pinfunction "B35_B35") (pintype "passive"))
    )
    (net (code "198") (name "unconnected-(J7-PadB36)") (class "Default")
      (node (ref "J7") (pin "B36") (pinfunction "B36_B36") (pintype "passive"))
    )
    (net (code "199") (name "unconnected-(J7-PadB37)") (class "Default")
      (node (ref "J7") (pin "B37") (pinfunction "B37_B37") (pintype "passive"))
    )
    (net (code "200") (name "unconnected-(J7-PadB38)") (class "Default")
      (node (ref "J7") (pin "B38") (pinfunction "B38_B38") (pintype "passive"))
    )
    (net (code "201") (name "unconnected-(J7-PadB39)") (class "Default")
      (node (ref "J7") (pin "B39") (pinfunction "B39_B39") (pintype "passive"))
    )
    (net (code "202") (name "unconnected-(J7-PadB40)") (class "Default")
      (node (ref "J7") (pin "B40") (pinfunction "B40_B40") (pintype "passive"))
    )
  )
)
